# pinout_v2.net
KiCad netlist of a schematic drawn in Altium Designer
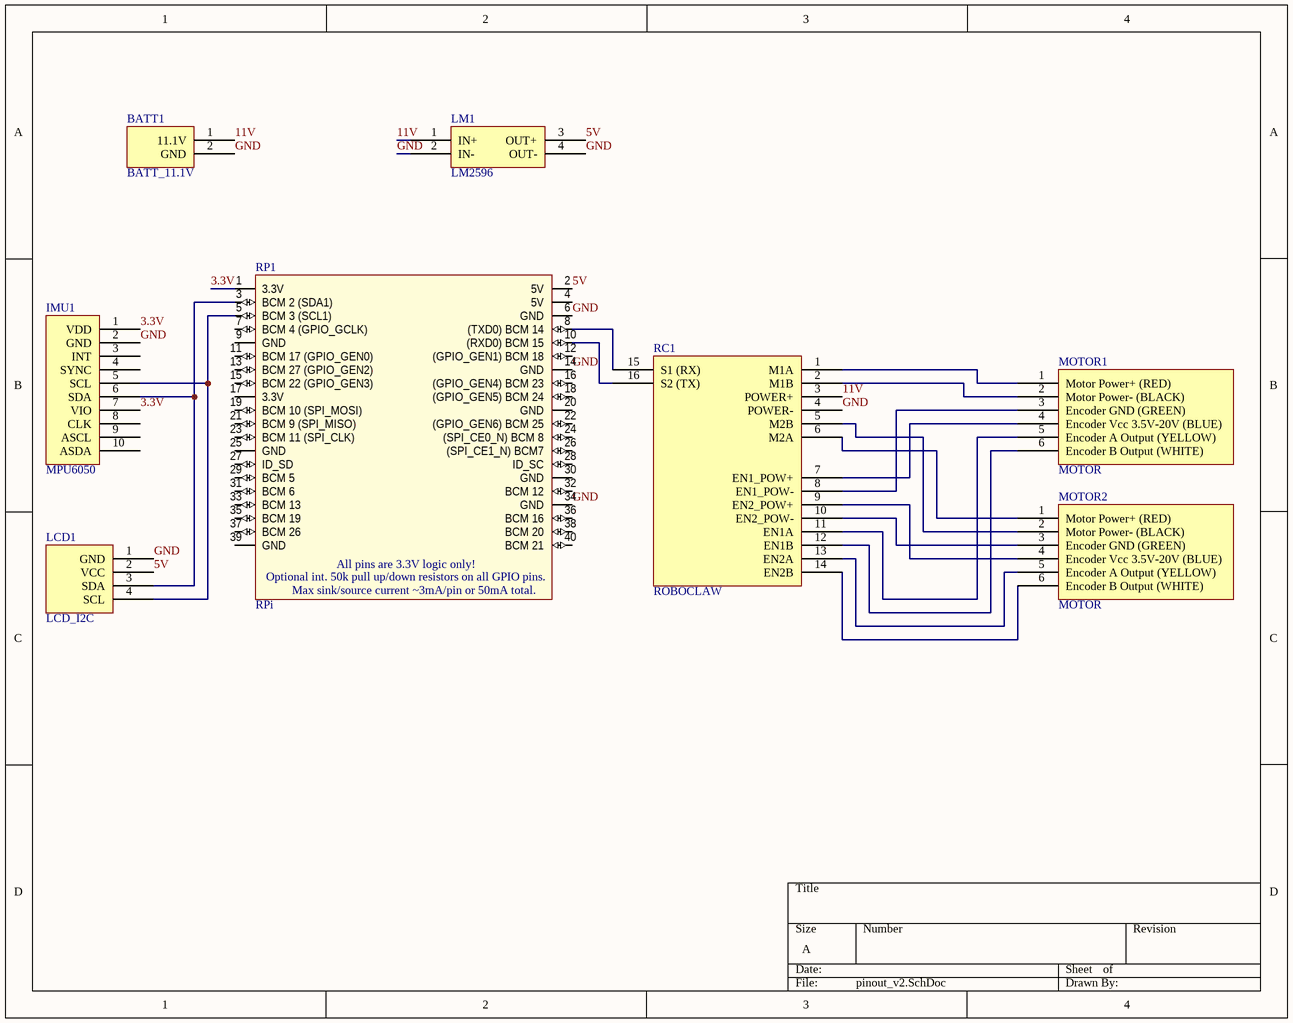
[diagram p0: pinout_v2.SchDoc]

(export (version "E")
  (design (tool "Eeschema 10.0.6"))
  (components
    (comp (ref "BATT1")
      (value "BATT_11.1V")
      (description "11.1V, 4000mAh, 40C 3S LiPo Battery")
      (libsource (lib "pinout") (part "BATT_11.1V"))
    )
    (comp (ref "IMU1")
      (value "MPU6050")
      (description "SparkFun Triple Axis Accelerometer and Gyro Breakout")
      (libsource (lib "pinout") (part "MPU6050"))
    )
    (comp (ref "LCD1")
      (value "LCD_I2C")
      (description "LCD with I2C communication")
      (libsource (lib "pinout") (part "LCD_I2C"))
    )
    (comp (ref "LM1") (value "LM2596") (libsource (lib "pinout") (part "LM2596")))
    (comp (ref "MOTOR1")
      (value "MOTOR")
      (description "30:1 Metal Gearmotor 37Dx68L mm with 64 CPR Encoder")
      (libsource (lib "pinout") (part "MOTOR"))
    )
    (comp (ref "MOTOR2")
      (value "MOTOR")
      (description "30:1 Metal Gearmotor 37Dx68L mm with 64 CPR Encoder")
      (libsource (lib "pinout") (part "MOTOR"))
    )
    (comp (ref "RC1")
      (value "ROBOCLAW")
      (description "RoboClaw 2x7A Motor Controller (V5C)")
      (libsource (lib "pinout") (part "ROBOCLAW"))
    )
    (comp (ref "RP1")
      (value "RPi")
      (footprint "40-Pin IDC Connector 2.54mm Pitch")
      (description "40-pin IDC 2.54mm P Header with RPi 2+ GPIO pinout")
      (fields (field (name "MOUSER PART #") "571-3-1761603-3"))
      (libsource (lib "pinout") (part "RPi"))
    )
  )
  (nets
    (net (code "1") (name "/3.3V") (class "Default")
      (node (ref "IMU1") (pin "1") (pinfunction "VDD_1") (pintype "passive"))
      (node (ref "IMU1") (pin "7") (pinfunction "VIO_7") (pintype "passive"))
      (node (ref "RP1") (pin "1") (pinfunction "3.3V_1") (pintype "power_in"))
    )
    (net (code "2") (name "/5V") (class "Default")
      (node (ref "LCD1") (pin "2") (pinfunction "VCC_2") (pintype "passive"))
      (node (ref "LM1") (pin "3") (pinfunction "OUT+_3") (pintype "passive"))
      (node (ref "RP1") (pin "2") (pinfunction "5V_2") (pintype "power_in"))
    )
    (net (code "3") (name "/11V") (class "Default")
      (node (ref "BATT1") (pin "1") (pinfunction "11.1V_1") (pintype "passive"))
      (node (ref "LM1") (pin "1") (pinfunction "IN+_1") (pintype "passive"))
      (node (ref "RC1") (pin "3") (pinfunction "POWER+_3") (pintype "passive"))
    )
    (net (code "4") (name "/GND") (class "Default")
      (node (ref "BATT1") (pin "2") (pinfunction "GND_2") (pintype "passive"))
      (node (ref "IMU1") (pin "2") (pinfunction "GND_2") (pintype "passive"))
      (node (ref "LCD1") (pin "1") (pinfunction "GND_1") (pintype "passive"))
      (node (ref "LM1") (pin "2") (pinfunction "IN-_2") (pintype "passive"))
      (node (ref "LM1") (pin "4") (pinfunction "OUT-_4") (pintype "passive"))
      (node (ref "RC1") (pin "4") (pinfunction "POWER-_4") (pintype "passive"))
      (node (ref "RP1") (pin "14") (pinfunction "GND_14") (pintype "power_in"))
      (node (ref "RP1") (pin "34") (pinfunction "GND_34") (pintype "power_in"))
      (node (ref "RP1") (pin "6") (pinfunction "GND_6") (pintype "power_in"))
    )
    (net (code "5") (name "Net-(IMU1-SCL)") (class "Default")
      (node (ref "IMU1") (pin "5") (pinfunction "SCL_5") (pintype "passive"))
      (node (ref "LCD1") (pin "4") (pinfunction "SCL_4") (pintype "passive"))
      (node (ref "RP1") (pin "5") (pinfunction "BCM_3_(SCL1)_5") (pintype "bidirectional"))
    )
    (net (code "6") (name "Net-(IMU1-SDA)") (class "Default")
      (node (ref "IMU1") (pin "6") (pinfunction "SDA_6") (pintype "passive"))
      (node (ref "LCD1") (pin "3") (pinfunction "SDA_3") (pintype "passive"))
      (node (ref "RP1") (pin "3") (pinfunction "BCM_2_(SDA1)_3") (pintype "bidirectional"))
    )
    (net (code "7") (name "Net-(MOTOR1-Encoder_A_Output_(YELLOW))") (class "Default")
      (node (ref "MOTOR1") (pin "5") (pinfunction "Encoder_A_Output_(YELLOW)_5") (pintype "passive"))
      (node (ref "RC1") (pin "11") (pinfunction "EN1A_11") (pintype "passive"))
    )
    (net (code "8") (name "Net-(MOTOR1-Encoder_B_Output_(WHITE))") (class "Default")
      (node (ref "MOTOR1") (pin "6") (pinfunction "Encoder_B_Output_(WHITE)_6") (pintype "passive"))
      (node (ref "RC1") (pin "12") (pinfunction "EN1B_12") (pintype "passive"))
    )
    (net (code "9") (name "Net-(MOTOR1-Encoder_GND_(GREEN))") (class "Default")
      (node (ref "MOTOR1") (pin "3") (pinfunction "Encoder_GND_(GREEN)_3") (pintype "passive"))
      (node (ref "RC1") (pin "8") (pinfunction "EN1_POW-_8") (pintype "passive"))
    )
    (net (code "10") (name "Net-(MOTOR1-Encoder_Vcc_3.5V-20V_(BLUE))") (class "Default")
      (node (ref "MOTOR1") (pin "4") (pinfunction "Encoder_Vcc_3.5V-20V_(BLUE)_4") (pintype "passive"))
      (node (ref "RC1") (pin "7") (pinfunction "EN1_POW+_7") (pintype "passive"))
    )
    (net (code "11") (name "Net-(MOTOR1-Motor_Power+_(RED))") (class "Default")
      (node (ref "MOTOR1") (pin "1") (pinfunction "Motor_Power+_(RED)_1") (pintype "passive"))
      (node (ref "RC1") (pin "1") (pinfunction "M1A_1") (pintype "passive"))
    )
    (net (code "12") (name "Net-(MOTOR1-Motor_Power-_(BLACK))") (class "Default")
      (node (ref "MOTOR1") (pin "2") (pinfunction "Motor_Power-_(BLACK)_2") (pintype "passive"))
      (node (ref "RC1") (pin "2") (pinfunction "M1B_2") (pintype "passive"))
    )
    (net (code "13") (name "Net-(MOTOR2-Encoder_A_Output_(YELLOW))") (class "Default")
      (node (ref "MOTOR2") (pin "5") (pinfunction "Encoder_A_Output_(YELLOW)_5") (pintype "passive"))
      (node (ref "RC1") (pin "13") (pinfunction "EN2A_13") (pintype "passive"))
    )
    (net (code "14") (name "Net-(MOTOR2-Encoder_B_Output_(WHITE))") (class "Default")
      (node (ref "MOTOR2") (pin "6") (pinfunction "Encoder_B_Output_(WHITE)_6") (pintype "passive"))
      (node (ref "RC1") (pin "14") (pinfunction "EN2B_14") (pintype "passive"))
    )
    (net (code "15") (name "Net-(MOTOR2-Encoder_GND_(GREEN))") (class "Default")
      (node (ref "MOTOR2") (pin "3") (pinfunction "Encoder_GND_(GREEN)_3") (pintype "passive"))
      (node (ref "RC1") (pin "10") (pinfunction "EN2_POW-_10") (pintype "passive"))
    )
    (net (code "16") (name "Net-(MOTOR2-Encoder_Vcc_3.5V-20V_(BLUE))") (class "Default")
      (node (ref "MOTOR2") (pin "4") (pinfunction "Encoder_Vcc_3.5V-20V_(BLUE)_4") (pintype "passive"))
      (node (ref "RC1") (pin "9") (pinfunction "EN2_POW+_9") (pintype "passive"))
    )
    (net (code "17") (name "Net-(MOTOR2-Motor_Power+_(RED))") (class "Default")
      (node (ref "MOTOR2") (pin "1") (pinfunction "Motor_Power+_(RED)_1") (pintype "passive"))
      (node (ref "RC1") (pin "6") (pinfunction "M2A_6") (pintype "passive"))
    )
    (net (code "18") (name "Net-(MOTOR2-Motor_Power-_(BLACK))") (class "Default")
      (node (ref "MOTOR2") (pin "2") (pinfunction "Motor_Power-_(BLACK)_2") (pintype "passive"))
      (node (ref "RC1") (pin "5") (pinfunction "M2B_5") (pintype "passive"))
    )
    (net (code "19") (name "Net-(RC1-S1_(RX))") (class "Default")
      (node (ref "RC1") (pin "15") (pinfunction "S1_(RX)_15") (pintype "passive"))
      (node (ref "RP1") (pin "8") (pinfunction "(TXD0)_BCM_14_8") (pintype "bidirectional"))
    )
    (net (code "20") (name "Net-(RC1-S2_(TX))") (class "Default")
      (node (ref "RC1") (pin "16") (pinfunction "S2_(TX)_16") (pintype "passive"))
      (node (ref "RP1") (pin "10") (pinfunction "(RXD0)_BCM_15_10") (pintype "bidirectional"))
    )
    (net (code "21") (name "unconnected-(IMU1-ASCL-Pad9)") (class "Default")
      (node (ref "IMU1") (pin "9") (pinfunction "ASCL_9") (pintype "passive"))
    )
    (net (code "22") (name "unconnected-(IMU1-ASDA-Pad10)") (class "Default")
      (node (ref "IMU1") (pin "10") (pinfunction "ASDA_10") (pintype "passive"))
    )
    (net (code "23") (name "unconnected-(IMU1-CLK-Pad8)") (class "Default")
      (node (ref "IMU1") (pin "8") (pinfunction "CLK_8") (pintype "passive"))
    )
    (net (code "24") (name "unconnected-(IMU1-INT-Pad3)") (class "Default")
      (node (ref "IMU1") (pin "3") (pinfunction "INT_3") (pintype "passive"))
    )
    (net (code "25") (name "unconnected-(IMU1-SYNC-Pad4)") (class "Default")
      (node (ref "IMU1") (pin "4") (pinfunction "SYNC_4") (pintype "passive"))
    )
    (net (code "26") (name "unconnected-(RP1-(GPIO_GEN1)_BCM_18-Pad12)") (class "Default")
      (node (ref "RP1") (pin "12") (pinfunction "(GPIO_GEN1)_BCM_18_12") (pintype "bidirectional"))
    )
    (net (code "27") (name "unconnected-(RP1-(GPIO_GEN4)_BCM_23-Pad16)") (class "Default")
      (node (ref "RP1") (pin "16") (pinfunction "(GPIO_GEN4)_BCM_23_16") (pintype "bidirectional"))
    )
    (net (code "28") (name "unconnected-(RP1-(GPIO_GEN5)_BCM_24-Pad18)") (class "Default")
      (node (ref "RP1") (pin "18") (pinfunction "(GPIO_GEN5)_BCM_24_18") (pintype "bidirectional"))
    )
    (net (code "29") (name "unconnected-(RP1-(GPIO_GEN6)_BCM_25-Pad22)") (class "Default")
      (node (ref "RP1") (pin "22") (pinfunction "(GPIO_GEN6)_BCM_25_22") (pintype "bidirectional"))
    )
    (net (code "30") (name "unconnected-(RP1-(SPI_CE0_N)_BCM_8-Pad24)") (class "Default")
      (node (ref "RP1") (pin "24") (pinfunction "(SPI_CE0_N)_BCM_8_24") (pintype "bidirectional"))
    )
    (net (code "31") (name "unconnected-(RP1-(SPI_CE1_N)_BCM7-Pad26)") (class "Default")
      (node (ref "RP1") (pin "26") (pinfunction "(SPI_CE1_N)_BCM7_26") (pintype "bidirectional"))
    )
    (net (code "32") (name "unconnected-(RP1-3.3V-Pad17)") (class "Default")
      (node (ref "RP1") (pin "17") (pinfunction "3.3V_17") (pintype "power_in"))
    )
    (net (code "33") (name "unconnected-(RP1-5V-Pad4)") (class "Default")
      (node (ref "RP1") (pin "4") (pinfunction "5V_4") (pintype "power_in"))
    )
    (net (code "34") (name "unconnected-(RP1-BCM_4_(GPIO_GCLK)-Pad7)") (class "Default")
      (node (ref "RP1") (pin "7") (pinfunction "BCM_4_(GPIO_GCLK)_7") (pintype "bidirectional"))
    )
    (net (code "35") (name "unconnected-(RP1-BCM_5-Pad29)") (class "Default")
      (node (ref "RP1") (pin "29") (pinfunction "BCM_5_29") (pintype "bidirectional"))
    )
    (net (code "36") (name "unconnected-(RP1-BCM_6-Pad31)") (class "Default")
      (node (ref "RP1") (pin "31") (pinfunction "BCM_6_31") (pintype "bidirectional"))
    )
    (net (code "37") (name "unconnected-(RP1-BCM_9_(SPI_MISO)-Pad21)") (class "Default")
      (node (ref "RP1") (pin "21") (pinfunction "BCM_9_(SPI_MISO)_21") (pintype "bidirectional"))
    )
    (net (code "38") (name "unconnected-(RP1-BCM_10_(SPI_MOSI)-Pad19)") (class "Default")
      (node (ref "RP1") (pin "19") (pinfunction "BCM_10_(SPI_MOSI)_19") (pintype "bidirectional"))
    )
    (net (code "39") (name "unconnected-(RP1-BCM_11_(SPI_CLK)-Pad23)") (class "Default")
      (node (ref "RP1") (pin "23") (pinfunction "BCM_11_(SPI_CLK)_23") (pintype "bidirectional"))
    )
    (net (code "40") (name "unconnected-(RP1-BCM_12-Pad32)") (class "Default")
      (node (ref "RP1") (pin "32") (pinfunction "BCM_12_32") (pintype "bidirectional"))
    )
    (net (code "41") (name "unconnected-(RP1-BCM_13-Pad33)") (class "Default")
      (node (ref "RP1") (pin "33") (pinfunction "BCM_13_33") (pintype "bidirectional"))
    )
    (net (code "42") (name "unconnected-(RP1-BCM_16-Pad36)") (class "Default")
      (node (ref "RP1") (pin "36") (pinfunction "BCM_16_36") (pintype "bidirectional"))
    )
    (net (code "43") (name "unconnected-(RP1-BCM_17_(GPIO_GEN0)-Pad11)") (class "Default")
      (node (ref "RP1") (pin "11") (pinfunction "BCM_17_(GPIO_GEN0)_11") (pintype "bidirectional"))
    )
    (net (code "44") (name "unconnected-(RP1-BCM_19-Pad35)") (class "Default")
      (node (ref "RP1") (pin "35") (pinfunction "BCM_19_35") (pintype "bidirectional"))
    )
    (net (code "45") (name "unconnected-(RP1-BCM_20-Pad38)") (class "Default")
      (node (ref "RP1") (pin "38") (pinfunction "BCM_20_38") (pintype "bidirectional"))
    )
    (net (code "46") (name "unconnected-(RP1-BCM_21-Pad40)") (class "Default")
      (node (ref "RP1") (pin "40") (pinfunction "BCM_21_40") (pintype "bidirectional"))
    )
    (net (code "47") (name "unconnected-(RP1-BCM_22_(GPIO_GEN3)-Pad15)") (class "Default")
      (node (ref "RP1") (pin "15") (pinfunction "BCM_22_(GPIO_GEN3)_15") (pintype "bidirectional"))
    )
    (net (code "48") (name "unconnected-(RP1-BCM_26-Pad37)") (class "Default")
      (node (ref "RP1") (pin "37") (pinfunction "BCM_26_37") (pintype "bidirectional"))
    )
    (net (code "49") (name "unconnected-(RP1-BCM_27_(GPIO_GEN2)-Pad13)") (class "Default")
      (node (ref "RP1") (pin "13") (pinfunction "BCM_27_(GPIO_GEN2)_13") (pintype "bidirectional"))
    )
    (net (code "50") (name "unconnected-(RP1-GND-Pad9)") (class "Default")
      (node (ref "RP1") (pin "9") (pinfunction "GND_9") (pintype "power_in"))
    )
    (net (code "51") (name "unconnected-(RP1-GND-Pad20)") (class "Default")
      (node (ref "RP1") (pin "20") (pinfunction "GND_20") (pintype "power_in"))
    )
    (net (code "52") (name "unconnected-(RP1-GND-Pad25)") (class "Default")
      (node (ref "RP1") (pin "25") (pinfunction "GND_25") (pintype "power_in"))
    )
    (net (code "53") (name "unconnected-(RP1-GND-Pad30)") (class "Default")
      (node (ref "RP1") (pin "30") (pinfunction "GND_30") (pintype "power_in"))
    )
    (net (code "54") (name "unconnected-(RP1-GND-Pad39)") (class "Default")
      (node (ref "RP1") (pin "39") (pinfunction "GND_39") (pintype "power_in"))
    )
    (net (code "55") (name "unconnected-(RP1-ID_SC-Pad28)") (class "Default")
      (node (ref "RP1") (pin "28") (pinfunction "ID_SC_28") (pintype "bidirectional"))
    )
    (net (code "56") (name "unconnected-(RP1-ID_SD-Pad27)") (class "Default")
      (node (ref "RP1") (pin "27") (pinfunction "ID_SD_27") (pintype "bidirectional"))
    )
  )
)
